# Power_12V.net
KiCad netlist of a schematic drawn in Altium Designer
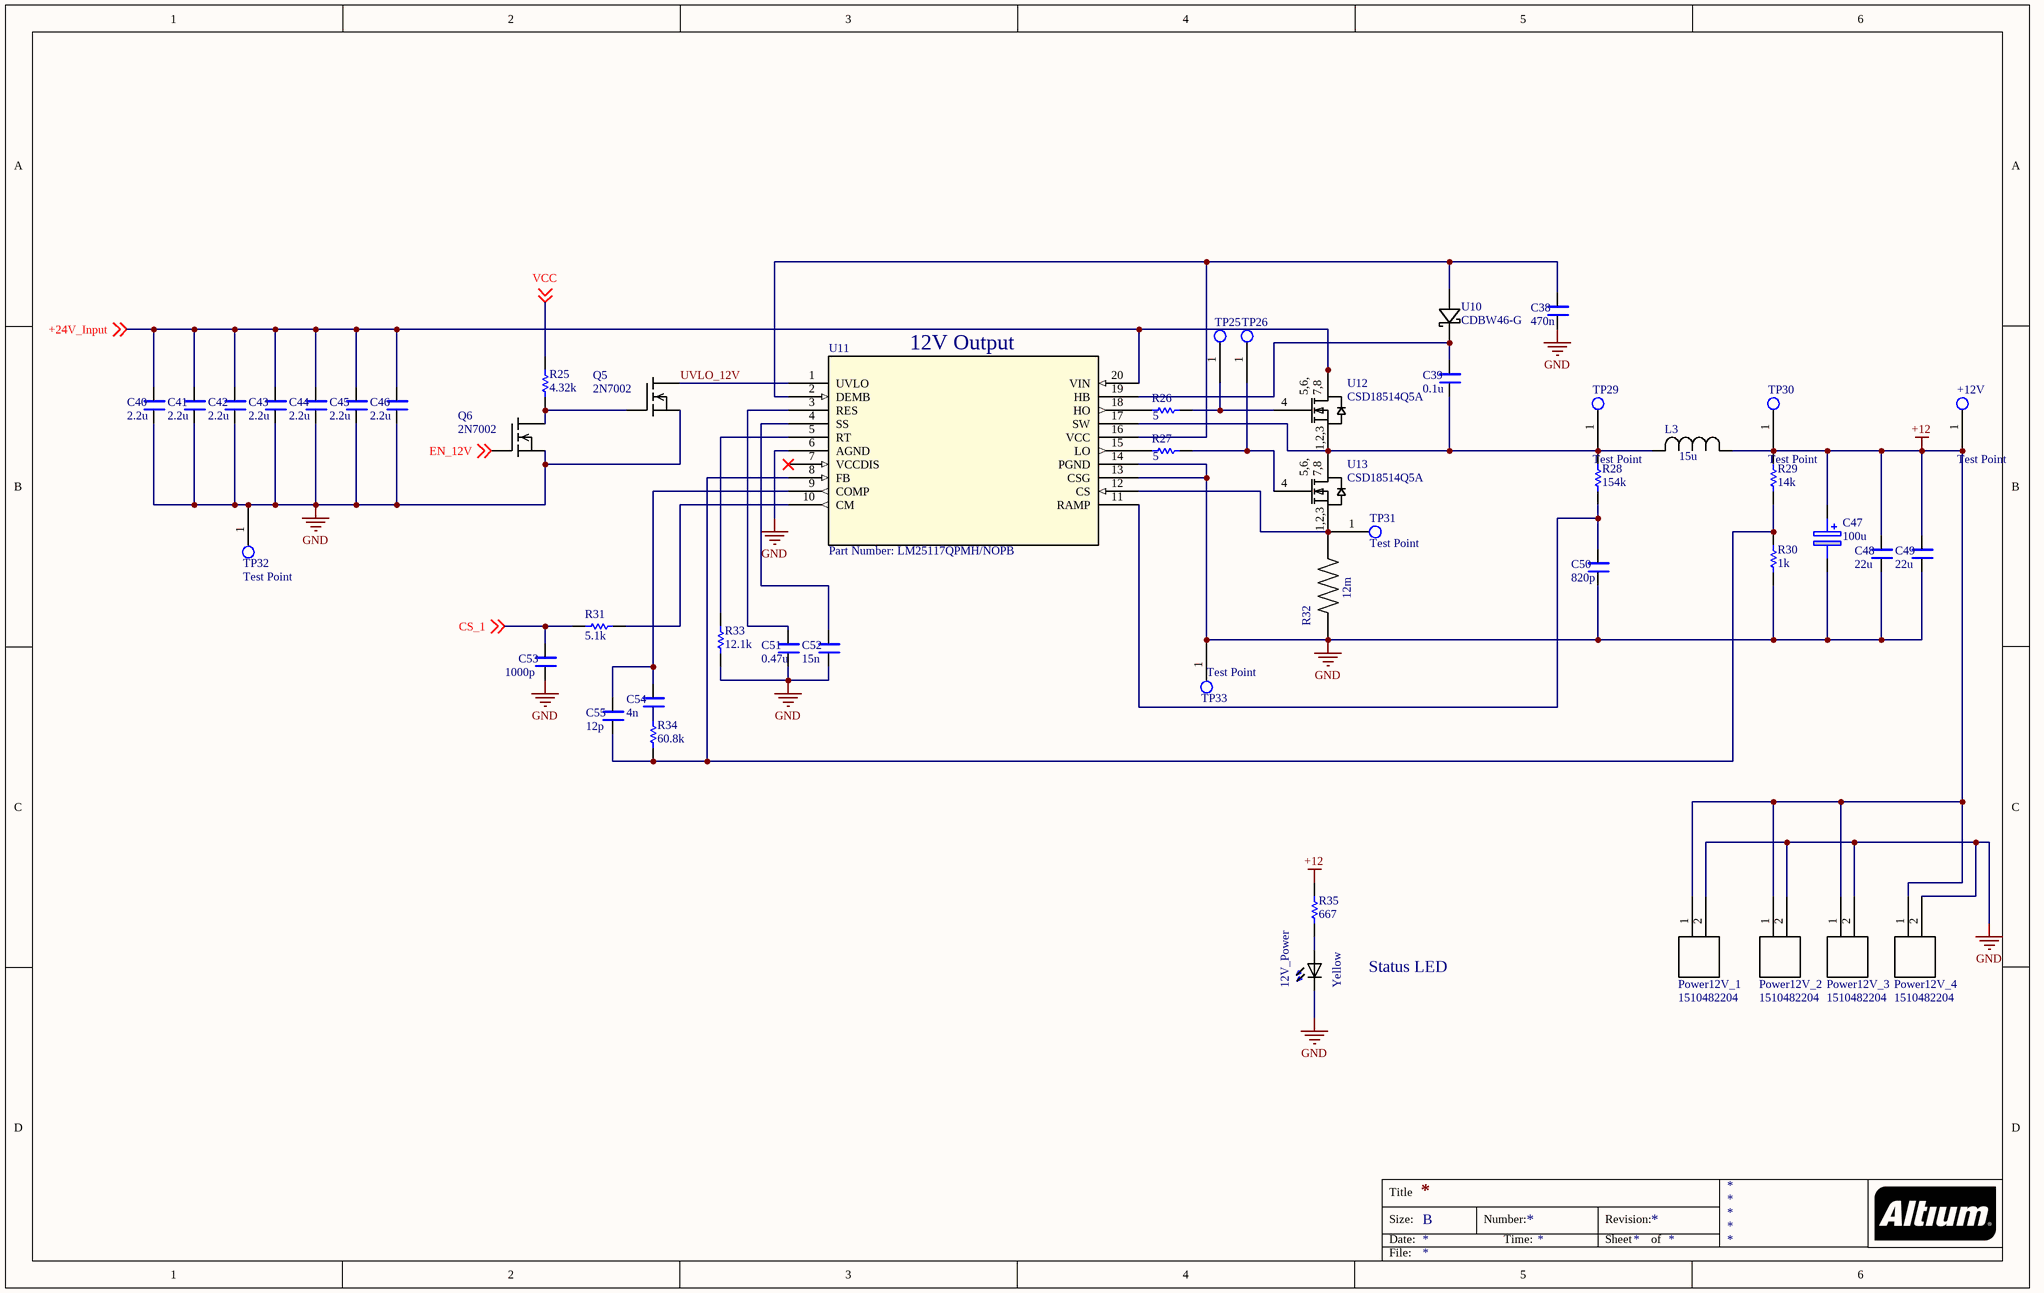
[diagram p0: Power_12V.SchDoc]

(export (version "E")
  (design (tool "Eeschema 10.0.6"))
  (components
    (comp (ref "+12V")
      (value "Test Point")
      (footprint "Test Point Through-hole")
      (libsource (lib "Test Points") (part "Test Point"))
    )
    (comp (ref "12V_Power")
      (value "Yellow")
      (footprint "*DIOC200X125X110_LTST-C171KSKT(Primary)")
      (description "Yellow 2 x 1.25 x 0.8 mm 130Â° Water Clear 50 mcd 2 V LED SMT")
      (fields (field (name "MP") "LTST-C171KSKT") (field (name "DIGI-KEY_PART_NUMBER") "160-1428-1-ND"))
      (libsource (lib "LTST-C171KSKT") (part "LTST-C171KSKT"))
    )
    (comp (ref "C38")
      (value "470n")
      (footprint "*CAPC2012X88N")
      (description "100pF Â±5% 250V Ceramic Capacitor C0G, NP0 0805 _2012 Metric_")
      (fields (field (name "MF") "KEMET") (field (name "DIGI-KEY_PART_NUMBER") "399-15000-1-ND"))
      (libsource (lib "C0805C101JAGAC7800") (part "C0805C101JAGAC7800"))
    )
    (comp (ref "C39")
      (value "0.1u")
      (footprint "*CAPC2012X88N")
      (description "100pF Â±5% 250V Ceramic Capacitor C0G, NP0 0805 _2012 Metric_")
      (fields (field (name "MF") "KEMET") (field (name "DIGI-KEY_PART_NUMBER") "399-15000-1-ND"))
      (libsource (lib "C0805C101JAGAC7800") (part "C0805C101JAGAC7800"))
    )
    (comp (ref "C40")
      (value "2.2u")
      (footprint "*CAPC2012X88N")
      (description "100pF Â±5% 250V Ceramic Capacitor C0G, NP0 0805 _2012 Metric_")
      (fields (field (name "MF") "KEMET") (field (name "DIGI-KEY_PART_NUMBER") "399-15000-1-ND"))
      (libsource (lib "C0805C101JAGAC7800") (part "C0805C101JAGAC7800"))
    )
    (comp (ref "C41")
      (value "2.2u")
      (footprint "*CAPC2012X88N")
      (description "100pF Â±5% 250V Ceramic Capacitor C0G, NP0 0805 _2012 Metric_")
      (fields (field (name "MF") "KEMET") (field (name "DIGI-KEY_PART_NUMBER") "399-15000-1-ND"))
      (libsource (lib "C0805C101JAGAC7800") (part "C0805C101JAGAC7800"))
    )
    (comp (ref "C42")
      (value "2.2u")
      (footprint "*CAPC2012X88N")
      (description "100pF Â±5% 250V Ceramic Capacitor C0G, NP0 0805 _2012 Metric_")
      (fields (field (name "MF") "KEMET") (field (name "DIGI-KEY_PART_NUMBER") "399-15000-1-ND"))
      (libsource (lib "C0805C101JAGAC7800") (part "C0805C101JAGAC7800"))
    )
    (comp (ref "C43")
      (value "2.2u")
      (footprint "*CAPC2012X88N")
      (description "100pF Â±5% 250V Ceramic Capacitor C0G, NP0 0805 _2012 Metric_")
      (fields (field (name "MF") "KEMET") (field (name "DIGI-KEY_PART_NUMBER") "399-15000-1-ND"))
      (libsource (lib "C0805C101JAGAC7800") (part "C0805C101JAGAC7800"))
    )
    (comp (ref "C44")
      (value "2.2u")
      (footprint "*CAPC2012X88N")
      (description "100pF Â±5% 250V Ceramic Capacitor C0G, NP0 0805 _2012 Metric_")
      (fields (field (name "MF") "KEMET") (field (name "DIGI-KEY_PART_NUMBER") "399-15000-1-ND"))
      (libsource (lib "C0805C101JAGAC7800") (part "C0805C101JAGAC7800"))
    )
    (comp (ref "C45")
      (value "2.2u")
      (footprint "*CAPC2012X88N")
      (description "100pF Â±5% 250V Ceramic Capacitor C0G, NP0 0805 _2012 Metric_")
      (fields (field (name "MF") "KEMET") (field (name "DIGI-KEY_PART_NUMBER") "399-15000-1-ND"))
      (libsource (lib "C0805C101JAGAC7800") (part "C0805C101JAGAC7800"))
    )
    (comp (ref "C46")
      (value "2.2u")
      (footprint "*CAPC2012X88N")
      (description "100pF Â±5% 250V Ceramic Capacitor C0G, NP0 0805 _2012 Metric_")
      (fields (field (name "MF") "KEMET") (field (name "DIGI-KEY_PART_NUMBER") "399-15000-1-ND"))
      (libsource (lib "C0805C101JAGAC7800") (part "C0805C101JAGAC7800"))
    )
    (comp (ref "C47")
      (value "100u")
      (footprint "CAPPRD500W65D1000H1800")
      (fields
        (field (name "MANUFACTURER_PART_NUMBER") "EEUFC1V331")
        (field (name "RS PART NUMBER") "1081337")
      )
      (libsource (lib "Power Distribution") (part "EEUFC1V331"))
    )
    (comp (ref "C48")
      (value "22u")
      (footprint "*CAPC2012X88N")
      (description "100pF Â±5% 250V Ceramic Capacitor C0G, NP0 0805 _2012 Metric_")
      (fields (field (name "MF") "KEMET") (field (name "DIGI-KEY_PART_NUMBER") "399-15000-1-ND"))
      (libsource (lib "C0805C101JAGAC7800") (part "C0805C101JAGAC7800"))
    )
    (comp (ref "C49")
      (value "22u")
      (footprint "*CAPC2012X88N")
      (description "100pF Â±5% 250V Ceramic Capacitor C0G, NP0 0805 _2012 Metric_")
      (fields (field (name "MF") "KEMET") (field (name "DIGI-KEY_PART_NUMBER") "399-15000-1-ND"))
      (libsource (lib "C0805C101JAGAC7800") (part "C0805C101JAGAC7800"))
    )
    (comp (ref "C50")
      (value "820p")
      (footprint "*CAPC2012X88N")
      (description "100pF Â±5% 250V Ceramic Capacitor C0G, NP0 0805 _2012 Metric_")
      (fields (field (name "MF") "KEMET") (field (name "DIGI-KEY_PART_NUMBER") "399-15000-1-ND"))
      (libsource (lib "C0805C101JAGAC7800") (part "C0805C101JAGAC7800"))
    )
    (comp (ref "C51")
      (value "0.47u")
      (footprint "*CAPC2012X88N")
      (description "100pF Â±5% 250V Ceramic Capacitor C0G, NP0 0805 _2012 Metric_")
      (fields (field (name "MF") "KEMET") (field (name "DIGI-KEY_PART_NUMBER") "399-15000-1-ND"))
      (libsource (lib "C0805C101JAGAC7800") (part "C0805C101JAGAC7800"))
    )
    (comp (ref "C52")
      (value "15n")
      (footprint "*CAPC2012X88N")
      (description "100pF Â±5% 250V Ceramic Capacitor C0G, NP0 0805 _2012 Metric_")
      (fields (field (name "MF") "KEMET") (field (name "DIGI-KEY_PART_NUMBER") "399-15000-1-ND"))
      (libsource (lib "C0805C101JAGAC7800") (part "C0805C101JAGAC7800"))
    )
    (comp (ref "C53")
      (value "1000p")
      (footprint "*CAPC2012X88N")
      (description "100pF Â±5% 250V Ceramic Capacitor C0G, NP0 0805 _2012 Metric_")
      (fields (field (name "MF") "KEMET") (field (name "DIGI-KEY_PART_NUMBER") "399-15000-1-ND"))
      (libsource (lib "C0805C101JAGAC7800") (part "C0805C101JAGAC7800"))
    )
    (comp (ref "C54")
      (value "4n")
      (footprint "*CAPC2012X88N")
      (description "100pF Â±5% 250V Ceramic Capacitor C0G, NP0 0805 _2012 Metric_")
      (fields (field (name "MF") "KEMET") (field (name "DIGI-KEY_PART_NUMBER") "399-15000-1-ND"))
      (libsource (lib "C0805C101JAGAC7800") (part "C0805C101JAGAC7800"))
    )
    (comp (ref "C55")
      (value "12p")
      (footprint "*CAPC2012X88N")
      (description "100pF Â±5% 250V Ceramic Capacitor C0G, NP0 0805 _2012 Metric_")
      (fields (field (name "MF") "KEMET") (field (name "DIGI-KEY_PART_NUMBER") "399-15000-1-ND"))
      (libsource (lib "C0805C101JAGAC7800") (part "C0805C101JAGAC7800"))
    )
    (comp (ref "L3")
      (value "15u")
      (footprint "IND_BOURNS_SRP12")
      (description "No Description Available")
      (fields
        (field (name "MANUFACTURER_PART_NUMBER") "SRP1270-6R8M")
        (field (name "COPYRIGHT") "Copyright (C) 2018 Accelerated Designs. All rights reserved")
      )
      (libsource (lib "2019-11-17_06-25-59") (part "Inductor-6.8uH"))
    )
    (comp (ref "Power12V_1")
      (value "1510482204")
      (footprint "1510482204")
      (description "Molex 6.5MM 2 pin connector, used for power connections. P/N 1510482204 and similar models.")
      (libsource (lib "Power Distribution") (part "1510482204"))
    )
    (comp (ref "Power12V_2")
      (value "1510482204")
      (footprint "1510482204")
      (description "Molex 6.5MM 2 pin connector, used for power connections. P/N 1510482204 and similar models.")
      (libsource (lib "Power Distribution") (part "1510482204"))
    )
    (comp (ref "Power12V_3")
      (value "1510482204")
      (footprint "1510482204")
      (description "Molex 6.5MM 2 pin connector, used for power connections. P/N 1510482204 and similar models.")
      (libsource (lib "Power Distribution") (part "1510482204"))
    )
    (comp (ref "Power12V_4")
      (value "1510482204")
      (footprint "1510482204")
      (description "Molex 6.5MM 2 pin connector, used for power connections. P/N 1510482204 and similar models.")
      (libsource (lib "Power Distribution") (part "1510482204"))
    )
    (comp (ref "Q5")
      (value "2N7002")
      (footprint "*SOT23")
      (description "Trans MOSFET N-CH 60V 0.115A 3-Pin SOT-23 T/R")
      (fields (field (name "MF") "ON Semiconductor"))
      (libsource (lib "2N7002") (part "2N7002"))
    )
    (comp (ref "Q6")
      (value "2N7002")
      (footprint "*SOT23")
      (description "Trans MOSFET N-CH 60V 0.115A 3-Pin SOT-23 T/R")
      (fields (field (name "MF") "ON Semiconductor"))
      (libsource (lib "2N7002") (part "2N7002"))
    )
    (comp (ref "R25")
      (value "4.32k")
      (footprint "RESC0805(2012)_M")
      (description "8M06 0.125W 1% 0805 (2012 Metric)  SMD")
      (fields (field (name "POWER") "0.125 W") (field (name "TOLERANCE") "1 %"))
      (libsource (lib "Altium Content Vault") (part "RES"))
    )
    (comp (ref "R26")
      (value "5")
      (footprint "AXIAL-0.3")
      (description "120R 0.125W 5% 0805 (2012 Metric)  SMD")
      (fields (field (name "TOLERANCE") "5 %") (field (name "POWER") "0.125 W"))
      (libsource (lib "Power Distribution") (part "120R 5% 0805"))
    )
    (comp (ref "R27")
      (value "5")
      (footprint "AXIAL-0.3")
      (description "120R 0.125W 5% 0805 (2012 Metric)  SMD")
      (fields (field (name "TOLERANCE") "5 %") (field (name "POWER") "0.125 W"))
      (libsource (lib "Power Distribution") (part "120R 5% 0805"))
    )
    (comp (ref "R28")
      (value "154k")
      (footprint "RESC0805(2012)_M")
      (description "8M06 0.125W 1% 0805 (2012 Metric)  SMD")
      (fields (field (name "POWER") "0.125 W") (field (name "TOLERANCE") "1 %"))
      (libsource (lib "Altium Content Vault") (part "RES"))
    )
    (comp (ref "R29")
      (value "14k")
      (footprint "RESC0805(2012)_M")
      (description "8M06 0.125W 1% 0805 (2012 Metric)  SMD")
      (fields (field (name "POWER") "0.125 W") (field (name "TOLERANCE") "1 %"))
      (libsource (lib "Altium Content Vault") (part "RES"))
    )
    (comp (ref "R30")
      (value "1k")
      (footprint "RESC0805(2012)_M")
      (description "8M06 0.125W 1% 0805 (2012 Metric)  SMD")
      (fields (field (name "POWER") "0.125 W") (field (name "TOLERANCE") "1 %"))
      (libsource (lib "Altium Content Vault") (part "RES"))
    )
    (comp (ref "R31")
      (value "5.1k")
      (footprint "RESC0805(2012)_M")
      (description "8M06 0.125W 1% 0805 (2012 Metric)  SMD")
      (fields (field (name "POWER") "0.125 W") (field (name "TOLERANCE") "1 %"))
      (libsource (lib "Altium Content Vault") (part "RES"))
    )
    (comp (ref "R32")
      (value "12m")
      (footprint "*RESC6432X110N")
      (description "Res Thick Film 2512 0.012 Ohm 1% 1W Pad SMD Automotive T/R")
      (fields (field (name "MP") "ERJ-M1WSF12MU") (field (name "DIGI-KEY_PART_NUMBER") "P12MCT-ND"))
      (libsource (lib "ERJ-M1WSF12MU") (part "ERJ-M1WSF12MU"))
    )
    (comp (ref "R33")
      (value "12.1k")
      (footprint "RESC0805(2012)_M")
      (description "8M06 0.125W 1% 0805 (2012 Metric)  SMD")
      (fields (field (name "POWER") "0.125 W") (field (name "TOLERANCE") "1 %"))
      (libsource (lib "Altium Content Vault") (part "RES"))
    )
    (comp (ref "R34")
      (value "60.8k")
      (footprint "RESC0805(2012)_M")
      (description "8M06 0.125W 1% 0805 (2012 Metric)  SMD")
      (fields (field (name "POWER") "0.125 W") (field (name "TOLERANCE") "1 %"))
      (libsource (lib "Altium Content Vault") (part "RES"))
    )
    (comp (ref "R35")
      (value "667")
      (footprint "RESC0805(2012)_M")
      (description "8M06 0.125W 1% 0805 (2012 Metric)  SMD")
      (fields (field (name "POWER") "0.125 W") (field (name "TOLERANCE") "1 %"))
      (libsource (lib "Altium Content Vault") (part "RES"))
    )
    (comp (ref "TP25")
      (value "~")
      (footprint "Test Point Through-hole")
      (libsource (lib "Test Points") (part "Test Point"))
    )
    (comp (ref "TP26")
      (value "~")
      (footprint "Test Point Through-hole")
      (libsource (lib "Test Points") (part "Test Point"))
    )
    (comp (ref "TP29")
      (value "Test Point")
      (footprint "Test Point Through-hole")
      (libsource (lib "Test Points") (part "Test Point"))
    )
    (comp (ref "TP30")
      (value "Test Point")
      (footprint "Test Point Through-hole")
      (libsource (lib "Test Points") (part "Test Point"))
    )
    (comp (ref "TP31")
      (value "Test Point")
      (footprint "Test Point Through-hole")
      (libsource (lib "Test Points") (part "Test Point"))
    )
    (comp (ref "TP32")
      (value "Test Point")
      (footprint "Test Point Through-hole")
      (libsource (lib "Test Points") (part "Test Point"))
    )
    (comp (ref "TP33")
      (value "Test Point")
      (footprint "Test Point Through-hole")
      (libsource (lib "Test Points") (part "Test Point"))
    )
    (comp (ref "U10")
      (value "CDBW46-G")
      (footprint "CDBW")
      (description "No Description Available")
      (fields (field (name "COPYRIGHT") "Copyright (C) 2018 Accelerated Designs. All rights reserved"))
      (libsource (lib "DIODE SCHOTTKY 100V 150MA") (part "CDBW46-G"))
    )
    (comp (ref "U11")
      (value "Part Number: LM25117QPMH/NOPB")
      (footprint "MXA20A")
      (description "No Description Available")
      (fields
        (field (name "MANUFACTURER") "Texas Instruments")
        (field (name "MANUFACTURER_PART_NUMBER") "LM25117QPMH/NOPB")
        (field (name "COPYRIGHT") "Copyright (C) 2018 Accelerated Designs. All rights reserved")
      )
      (libsource (lib "2019-11-16_22-35-15") (part "LM25117QPMH/NOPB"))
    )
    (comp (ref "U12")
      (value "CSD18514Q5A")
      (footprint "DQJ0008A")
      (description "No Description Available")
      (fields (field (name "COPYRIGHT") "Copyright (C) 2018 Accelerated Designs. All rights reserved"))
      (libsource (lib "ul_CSD18514Q5A") (part "CSD18514Q5A"))
    )
    (comp (ref "U13")
      (value "CSD18514Q5A")
      (footprint "DQJ0008A")
      (description "No Description Available")
      (fields (field (name "COPYRIGHT") "Copyright (C) 2018 Accelerated Designs. All rights reserved"))
      (libsource (lib "ul_CSD18514Q5A") (part "CSD18514Q5A"))
    )
  )
  (nets
    (net (code "1") (name "+12") (class "Default")
      (node (ref "+12V") (pin "1") (pinfunction "1_1") (pintype "passive"))
      (node (ref "C47") (pin "1") (pinfunction "+_1") (pintype "passive"))
      (node (ref "C48") (pin "2") (pinfunction "2_2") (pintype "passive"))
      (node (ref "C49") (pin "2") (pinfunction "2_2") (pintype "passive"))
      (node (ref "L3") (pin "1") (pinfunction "1_1") (pintype "passive"))
      (node (ref "Power12V_1") (pin "1") (pintype "passive"))
      (node (ref "Power12V_2") (pin "1") (pintype "passive"))
      (node (ref "Power12V_3") (pin "1") (pintype "passive"))
      (node (ref "Power12V_4") (pin "1") (pintype "passive"))
      (node (ref "R29") (pin "2") (pinfunction "2_2") (pintype "passive"))
      (node (ref "R35") (pin "2") (pinfunction "2_2") (pintype "passive"))
      (node (ref "TP30") (pin "1") (pinfunction "1_1") (pintype "passive"))
    )
    (net (code "2") (name "+24V_Input") (class "Default")
      (node (ref "C40") (pin "2") (pinfunction "2_2") (pintype "passive"))
      (node (ref "C41") (pin "2") (pinfunction "2_2") (pintype "passive"))
      (node (ref "C42") (pin "2") (pinfunction "2_2") (pintype "passive"))
      (node (ref "C43") (pin "2") (pinfunction "2_2") (pintype "passive"))
      (node (ref "C44") (pin "2") (pinfunction "2_2") (pintype "passive"))
      (node (ref "C45") (pin "2") (pinfunction "2_2") (pintype "passive"))
      (node (ref "C46") (pin "2") (pinfunction "2_2") (pintype "passive"))
      (node (ref "U11") (pin "20") (pinfunction "VIN_20") (pintype "input"))
      (node (ref "U12") (pin "5") (pinfunction "D_5") (pintype "passive"))
      (node (ref "U12") (pin "6") (pinfunction "D_6") (pintype "passive"))
      (node (ref "U12") (pin "7") (pinfunction "D_7") (pintype "passive"))
      (node (ref "U12") (pin "8") (pinfunction "D_8") (pintype "passive"))
    )
    (net (code "3") (name "/UVLO_12V") (class "Default")
      (node (ref "Q5") (pin "3") (pinfunction "D_3") (pintype "passive"))
      (node (ref "U11") (pin "1") (pinfunction "UVLO_1") (pintype "passive"))
    )
    (net (code "4") (name "CS_1") (class "Default")
      (node (ref "C53") (pin "2") (pinfunction "2_2") (pintype "passive"))
      (node (ref "R31") (pin "2") (pinfunction "2_2") (pintype "passive"))
    )
    (net (code "5") (name "EN_12V") (class "Default")
      (node (ref "Q6") (pin "1") (pinfunction "G_1") (pintype "passive"))
    )
    (net (code "6") (name "GND") (class "Default")
      (node (ref "12V_Power") (pin "NEG") (pinfunction "NEG_NEG") (pintype "passive"))
      (node (ref "C38") (pin "1") (pinfunction "1_1") (pintype "passive"))
      (node (ref "C40") (pin "1") (pinfunction "1_1") (pintype "passive"))
      (node (ref "C41") (pin "1") (pinfunction "1_1") (pintype "passive"))
      (node (ref "C42") (pin "1") (pinfunction "1_1") (pintype "passive"))
      (node (ref "C43") (pin "1") (pinfunction "1_1") (pintype "passive"))
      (node (ref "C44") (pin "1") (pinfunction "1_1") (pintype "passive"))
      (node (ref "C45") (pin "1") (pinfunction "1_1") (pintype "passive"))
      (node (ref "C46") (pin "1") (pinfunction "1_1") (pintype "passive"))
      (node (ref "C47") (pin "2") (pinfunction "-_2") (pintype "passive"))
      (node (ref "C48") (pin "1") (pinfunction "1_1") (pintype "passive"))
      (node (ref "C49") (pin "1") (pinfunction "1_1") (pintype "passive"))
      (node (ref "C50") (pin "1") (pinfunction "1_1") (pintype "passive"))
      (node (ref "C51") (pin "1") (pinfunction "1_1") (pintype "passive"))
      (node (ref "C52") (pin "1") (pinfunction "1_1") (pintype "passive"))
      (node (ref "C53") (pin "1") (pinfunction "1_1") (pintype "passive"))
      (node (ref "Power12V_1") (pin "2") (pintype "passive"))
      (node (ref "Power12V_2") (pin "2") (pintype "passive"))
      (node (ref "Power12V_3") (pin "2") (pintype "passive"))
      (node (ref "Power12V_4") (pin "2") (pintype "passive"))
      (node (ref "Q5") (pin "2") (pinfunction "S_2") (pintype "passive"))
      (node (ref "Q6") (pin "2") (pinfunction "S_2") (pintype "passive"))
      (node (ref "R30") (pin "1") (pinfunction "1_1") (pintype "passive"))
      (node (ref "R32") (pin "1") (pinfunction "1_1") (pintype "passive"))
      (node (ref "R33") (pin "1") (pinfunction "1_1") (pintype "passive"))
      (node (ref "TP32") (pin "1") (pinfunction "1_1") (pintype "passive"))
      (node (ref "TP33") (pin "1") (pinfunction "1_1") (pintype "passive"))
      (node (ref "U11") (pin "13") (pinfunction "CSG_13") (pintype "passive"))
      (node (ref "U11") (pin "14") (pinfunction "PGND_14") (pintype "power_in"))
      (node (ref "U11") (pin "6") (pinfunction "AGND_6") (pintype "power_in"))
    )
    (net (code "7") (name "Net-(12V_Power-PadPOS)") (class "Default")
      (node (ref "12V_Power") (pin "POS") (pinfunction "POS_POS") (pintype "passive"))
      (node (ref "R35") (pin "1") (pinfunction "1_1") (pintype "passive"))
    )
    (net (code "8") (name "Net-(C54-Pad1)") (class "Default")
      (node (ref "C54") (pin "1") (pinfunction "1_1") (pintype "passive"))
      (node (ref "R34") (pin "2") (pinfunction "2_2") (pintype "passive"))
    )
    (net (code "9") (name "Net-(Q5-G)") (class "Default")
      (node (ref "Q5") (pin "1") (pinfunction "G_1") (pintype "passive"))
      (node (ref "Q6") (pin "3") (pinfunction "D_3") (pintype "passive"))
      (node (ref "R25") (pin "1") (pinfunction "1_1") (pintype "passive"))
    )
    (net (code "10") (name "Net-(U11-CM)") (class "Default")
      (node (ref "R31") (pin "1") (pinfunction "1_1") (pintype "passive"))
      (node (ref "U11") (pin "10") (pinfunction "CM_10") (pintype "output"))
    )
    (net (code "11") (name "Net-(U11-COMP)") (class "Default")
      (node (ref "C54") (pin "2") (pinfunction "2_2") (pintype "passive"))
      (node (ref "C55") (pin "2") (pinfunction "2_2") (pintype "passive"))
      (node (ref "U11") (pin "9") (pinfunction "COMP_9") (pintype "output"))
    )
    (net (code "12") (name "Net-(U11-CS)") (class "Default")
      (node (ref "R32") (pin "2") (pinfunction "2_2") (pintype "passive"))
      (node (ref "TP31") (pin "1") (pinfunction "1_1") (pintype "passive"))
      (node (ref "U11") (pin "12") (pinfunction "CS_12") (pintype "input"))
      (node (ref "U13") (pin "1") (pinfunction "S_1") (pintype "passive"))
      (node (ref "U13") (pin "2") (pinfunction "S_2") (pintype "passive"))
      (node (ref "U13") (pin "3") (pinfunction "S_3") (pintype "passive"))
    )
    (net (code "13") (name "Net-(U11-DEMB)") (class "Default")
      (node (ref "C38") (pin "2") (pinfunction "2_2") (pintype "passive"))
      (node (ref "U10") (pin "2") (pinfunction "2_2") (pintype "passive"))
      (node (ref "U11") (pin "16") (pinfunction "VCC_16") (pintype "power_in"))
      (node (ref "U11") (pin "2") (pinfunction "DEMB_2") (pintype "input"))
    )
    (net (code "14") (name "Net-(U11-FB)") (class "Default")
      (node (ref "C55") (pin "1") (pinfunction "1_1") (pintype "passive"))
      (node (ref "R29") (pin "1") (pinfunction "1_1") (pintype "passive"))
      (node (ref "R30") (pin "2") (pinfunction "2_2") (pintype "passive"))
      (node (ref "R34") (pin "1") (pinfunction "1_1") (pintype "passive"))
      (node (ref "U11") (pin "8") (pinfunction "FB_8") (pintype "input"))
    )
    (net (code "15") (name "Net-(U11-HB)") (class "Default")
      (node (ref "C39") (pin "2") (pinfunction "2_2") (pintype "passive"))
      (node (ref "U10") (pin "1") (pinfunction "1_1") (pintype "passive"))
      (node (ref "U11") (pin "19") (pinfunction "HB_19") (pintype "passive"))
    )
    (net (code "16") (name "Net-(U11-HO)") (class "Default")
      (node (ref "R26") (pin "1") (pinfunction "1_1") (pintype "passive"))
      (node (ref "U11") (pin "18") (pinfunction "HO_18") (pintype "output"))
    )
    (net (code "17") (name "Net-(U11-LO)") (class "Default")
      (node (ref "R27") (pin "1") (pinfunction "1_1") (pintype "passive"))
      (node (ref "U11") (pin "15") (pinfunction "LO_15") (pintype "output"))
    )
    (net (code "18") (name "Net-(U11-RAMP)") (class "Default")
      (node (ref "C50") (pin "2") (pinfunction "2_2") (pintype "passive"))
      (node (ref "R28") (pin "1") (pinfunction "1_1") (pintype "passive"))
      (node (ref "U11") (pin "11") (pinfunction "RAMP_11") (pintype "passive"))
    )
    (net (code "19") (name "Net-(U11-RES)") (class "Default")
      (node (ref "C51") (pin "2") (pinfunction "2_2") (pintype "passive"))
      (node (ref "U11") (pin "3") (pinfunction "RES_3") (pintype "passive"))
    )
    (net (code "20") (name "Net-(U11-RT)") (class "Default")
      (node (ref "R33") (pin "2") (pinfunction "2_2") (pintype "passive"))
      (node (ref "U11") (pin "5") (pinfunction "RT_5") (pintype "passive"))
    )
    (net (code "21") (name "Net-(U11-SS)") (class "Default")
      (node (ref "C52") (pin "2") (pinfunction "2_2") (pintype "passive"))
      (node (ref "U11") (pin "4") (pinfunction "SS_4") (pintype "passive"))
    )
    (net (code "22") (name "Net-(U11-SW)") (class "Default")
      (node (ref "C39") (pin "1") (pinfunction "1_1") (pintype "passive"))
      (node (ref "L3") (pin "2") (pinfunction "2_2") (pintype "passive"))
      (node (ref "R28") (pin "2") (pinfunction "2_2") (pintype "passive"))
      (node (ref "TP29") (pin "1") (pinfunction "1_1") (pintype "passive"))
      (node (ref "U11") (pin "17") (pinfunction "SW_17") (pintype "passive"))
      (node (ref "U12") (pin "1") (pinfunction "S_1") (pintype "passive"))
      (node (ref "U12") (pin "2") (pinfunction "S_2") (pintype "passive"))
      (node (ref "U12") (pin "3") (pinfunction "S_3") (pintype "passive"))
      (node (ref "U13") (pin "5") (pinfunction "D_5") (pintype "passive"))
      (node (ref "U13") (pin "6") (pinfunction "D_6") (pintype "passive"))
      (node (ref "U13") (pin "7") (pinfunction "D_7") (pintype "passive"))
      (node (ref "U13") (pin "8") (pinfunction "D_8") (pintype "passive"))
    )
    (net (code "23") (name "Net-(U12-G)") (class "Default")
      (node (ref "R26") (pin "2") (pinfunction "2_2") (pintype "passive"))
      (node (ref "TP25") (pin "1") (pinfunction "1_1") (pintype "passive"))
      (node (ref "U12") (pin "4") (pinfunction "G_4") (pintype "passive"))
    )
    (net (code "24") (name "Net-(U13-G)") (class "Default")
      (node (ref "R27") (pin "2") (pinfunction "2_2") (pintype "passive"))
      (node (ref "TP26") (pin "1") (pinfunction "1_1") (pintype "passive"))
      (node (ref "U13") (pin "4") (pinfunction "G_4") (pintype "passive"))
    )
    (net (code "25") (name "VCC") (class "Default")
      (node (ref "R25") (pin "2") (pinfunction "2_2") (pintype "passive"))
    )
    (net (code "26") (name "unconnected-(U11-VCCDIS-Pad7)") (class "Default")
      (node (ref "U11") (pin "7") (pinfunction "VCCDIS_7") (pintype "input+no_connect"))
    )
  )
)
